# emg-ps-usb_rev1.net
KiCad netlist of a schematic drawn in EAGLE
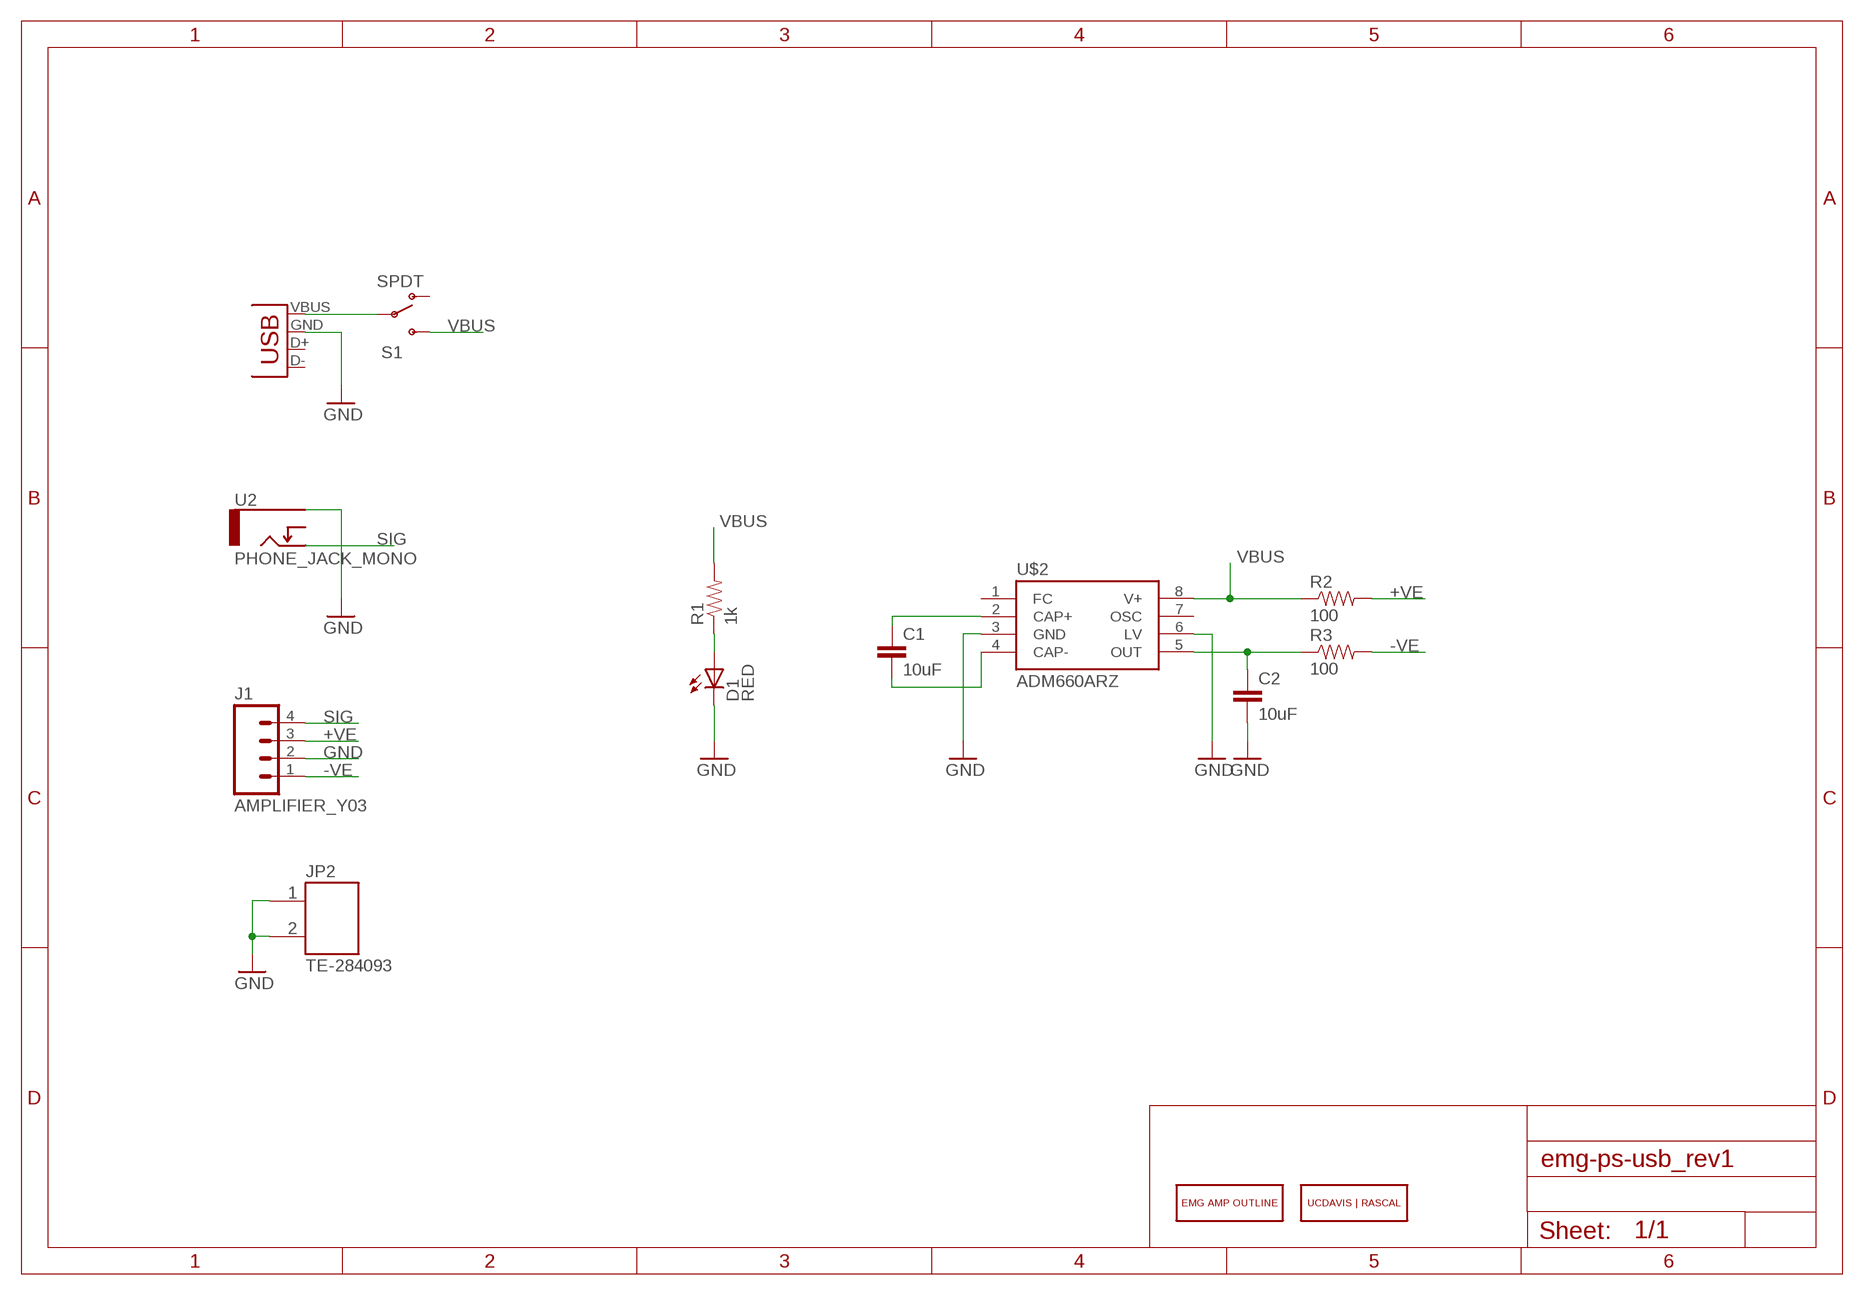
[diagram p0: schematic, sheet 1]

(export (version "E")
  (design (tool "Eeschema 10.0.6"))
  (components
    (comp (ref "C1")
      (value "10uF")
      (footprint "eagle-import:0805")
      (libsource (lib "eagle-import") (part "CAP0805"))
    )
    (comp (ref "C2")
      (value "10uF")
      (footprint "eagle-import:0805")
      (libsource (lib "eagle-import") (part "CAP0805"))
    )
    (comp (ref "D1")
      (value "RED")
      (footprint "eagle-import:LED-0603")
      (libsource (lib "eagle-import") (part "LED-RED0603"))
    )
    (comp (ref "J1")
      (value "AMPLIFIER_Y03")
      (footprint "eagle-import:AMPLIFIER_WTB")
      (libsource (lib "eagle-import") (part "AMPLIFIER_Y03"))
    )
    (comp (ref "JP1")
      (value "USB-A-H")
      (footprint "eagle-import:USB-A-H")
      (libsource (lib "eagle-import") (part "USB-A-H"))
    )
    (comp (ref "JP2")
      (value "TE-284093")
      (footprint "eagle-import:TE-284093")
      (libsource (lib "eagle-import") (part "TE-284093"))
    )
    (comp (ref "R1")
      (value "1k")
      (footprint "eagle-import:0805")
      (libsource (lib "eagle-import") (part "RESISTOR0805-RES"))
    )
    (comp (ref "R2")
      (value "100")
      (footprint "eagle-import:0805")
      (libsource (lib "eagle-import") (part "RESISTOR0805-RES"))
    )
    (comp (ref "R3")
      (value "100")
      (footprint "eagle-import:0805")
      (libsource (lib "eagle-import") (part "RESISTOR0805-RES"))
    )
    (comp (ref "S1")
      (value "SPDT")
      (footprint "eagle-import:SWITCH-SPST-SMD-A")
      (libsource (lib "eagle-import") (part "SWITCH-SPDT-SMD-A"))
    )
    (comp (ref "U$1")
      (value "UCDAVIS-RASCAL_LOGO-2LINE")
      (footprint "eagle-import:UCDAVIS-RASCAL_LOGO")
      (libsource (lib "eagle-import") (part "UCDAVIS-RASCAL_LOGO-2LINE"))
    )
    (comp (ref "U$2")
      (value "ADM660ARZ")
      (footprint "eagle-import:SOIC8")
      (libsource (lib "eagle-import") (part "ADM660ARZ"))
    )
    (comp (ref "U$3")
      (value "EMG_AMP_OUTLINE-Y03ENDS")
      (footprint "eagle-import:EMG_Y03_OUTLINEENDS")
      (libsource (lib "eagle-import") (part "EMG_AMP_OUTLINE-Y03ENDS"))
    )
    (comp (ref "U2")
      (value "PHONE_JACK_MONO")
      (footprint "eagle-import:MJ-3523-SMT")
      (libsource (lib "eagle-import") (part "PHONE_JACK_MONO"))
    )
  )
  (nets
    (net (code "1") (name "/+VE") (class "Default")
      (node (ref "J1") (pin "3") (pinfunction "3_3") (pintype "passive"))
      (node (ref "R2") (pin "2") (pinfunction "2_2") (pintype "passive"))
    )
    (net (code "2") (name "/-VE") (class "Default")
      (node (ref "J1") (pin "1") (pinfunction "1_1") (pintype "passive"))
      (node (ref "R3") (pin "2") (pinfunction "2_2") (pintype "passive"))
    )
    (net (code "3") (name "/SIG") (class "Default")
      (node (ref "J1") (pin "4") (pinfunction "4_4") (pintype "passive"))
      (node (ref "U2") (pin "P$2") (pinfunction "P$2_P$2") (pintype "bidirectional"))
    )
    (net (code "4") (name "/VBUS") (class "Default")
      (node (ref "R1") (pin "2") (pinfunction "2_2") (pintype "passive"))
      (node (ref "R2") (pin "1") (pinfunction "1_1") (pintype "passive"))
      (node (ref "S1") (pin "3") (pinfunction "S_3") (pintype "passive"))
      (node (ref "U$2") (pin "8") (pinfunction "V+_8") (pintype "bidirectional"))
    )
    (net (code "5") (name "GND") (class "Default")
      (node (ref "C2") (pin "2") (pinfunction "2_2") (pintype "passive"))
      (node (ref "D1") (pin "C") (pinfunction "C_C") (pintype "passive"))
      (node (ref "J1") (pin "2") (pinfunction "2_2") (pintype "passive"))
      (node (ref "JP1") (pin "GND") (pinfunction "VBUS_GND") (pintype "bidirectional"))
      (node (ref "JP2") (pin "P$1") (pinfunction "1_P$1") (pintype "bidirectional"))
      (node (ref "JP2") (pin "P$2") (pinfunction "2_P$2") (pintype "bidirectional"))
      (node (ref "U$2") (pin "3") (pinfunction "GND_3") (pintype "bidirectional"))
      (node (ref "U$2") (pin "6") (pinfunction "LV_6") (pintype "bidirectional"))
      (node (ref "U2") (pin "P$1") (pinfunction "P$1_P$1") (pintype "bidirectional"))
    )
    (net (code "6") (name "Net-(D1-PadA)") (class "Default")
      (node (ref "D1") (pin "A") (pinfunction "A_A") (pintype "passive"))
      (node (ref "R1") (pin "1") (pinfunction "1_1") (pintype "passive"))
    )
    (net (code "7") (name "Net-(JP1-GND)") (class "Default")
      (node (ref "JP1") (pin "VBUS") (pinfunction "GND_VBUS") (pintype "bidirectional"))
      (node (ref "S1") (pin "2") (pinfunction "P_2") (pintype "passive"))
    )
    (net (code "8") (name "Net-(U$2-CAP+)") (class "Default")
      (node (ref "C1") (pin "1") (pinfunction "1_1") (pintype "passive"))
      (node (ref "U$2") (pin "2") (pinfunction "CAP+_2") (pintype "bidirectional"))
    )
    (net (code "9") (name "Net-(U$2-CAP-)") (class "Default")
      (node (ref "C1") (pin "2") (pinfunction "2_2") (pintype "passive"))
      (node (ref "U$2") (pin "4") (pinfunction "CAP-_4") (pintype "bidirectional"))
    )
    (net (code "10") (name "Net-(U$2-OUT)") (class "Default")
      (node (ref "C2") (pin "1") (pinfunction "1_1") (pintype "passive"))
      (node (ref "R3") (pin "1") (pinfunction "1_1") (pintype "passive"))
      (node (ref "U$2") (pin "5") (pinfunction "OUT_5") (pintype "bidirectional"))
    )
    (net (code "11") (name "unconnected-(JP1-D+-PadD-)") (class "Default")
      (node (ref "JP1") (pin "D-") (pinfunction "D+_D-") (pintype "bidirectional"))
    )
    (net (code "12") (name "unconnected-(JP1-D--PadD+)") (class "Default")
      (node (ref "JP1") (pin "D+") (pinfunction "D-_D+") (pintype "bidirectional"))
    )
    (net (code "13") (name "unconnected-(S1-O-Pad1)") (class "Default")
      (node (ref "S1") (pin "1") (pinfunction "O_1") (pintype "passive"))
    )
    (net (code "14") (name "unconnected-(U$2-FC-Pad1)") (class "Default")
      (node (ref "U$2") (pin "1") (pinfunction "FC_1") (pintype "bidirectional"))
    )
    (net (code "15") (name "unconnected-(U$2-OSC-Pad7)") (class "Default")
      (node (ref "U$2") (pin "7") (pinfunction "OSC_7") (pintype "bidirectional"))
    )
    (net (code "16") (name "unconnected-(U2-PadP$3)") (class "Default")
      (node (ref "U2") (pin "P$3") (pinfunction "P$3_P$3") (pintype "bidirectional"))
    )
  )
)
